# dataBoard.net
KiCad netlist of a schematic drawn in EAGLE
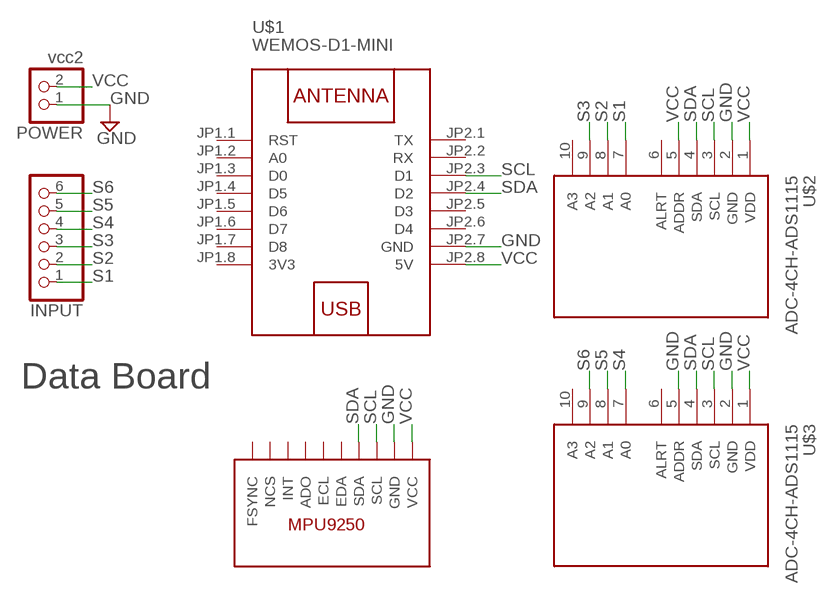
[diagram p0: schematic, sheet 1]

(export (version "E")
  (design (tool "Eeschema 10.0.6"))
  (components
    (comp (ref "INPUT")
      (value "PINHD-1X6")
      (footprint "eagle-import:1X06")
      (libsource (lib "eagle-import") (part "PINHD-1X6"))
    )
    (comp (ref "MPU1")
      (value "MPU9250")
      (footprint "eagle-import:MPU9250")
      (libsource (lib "eagle-import") (part "MPU9250"))
    )
    (comp (ref "POWER")
      (value "vcc2")
      (footprint "eagle-import:1X02")
      (libsource (lib "eagle-import") (part "PINHD-1X2"))
    )
    (comp (ref "U$1")
      (value "WEMOS-D1-MINI")
      (footprint "eagle-import:WEMOS-D1-MINI")
      (libsource (lib "eagle-import") (part "WEMOS-D1-MINI"))
    )
    (comp (ref "U$2")
      (value "ADC-4CH-ADS1115")
      (footprint "eagle-import:ADC-4CH-ADS1115")
      (libsource (lib "eagle-import") (part "ADC-4CH-ADS1115"))
    )
    (comp (ref "U$3")
      (value "ADC-4CH-ADS1115")
      (footprint "eagle-import:ADC-4CH-ADS1115")
      (libsource (lib "eagle-import") (part "ADC-4CH-ADS1115"))
    )
  )
  (nets
    (net (code "1") (name "/3V3") (class "Default")
      (node (ref "U$1") (pin "JP1.8") (pinfunction "3V3_JP1.8") (pintype "power_in"))
    )
    (net (code "2") (name "/S1") (class "Default")
      (node (ref "INPUT") (pin "1") (pinfunction "1_1") (pintype "passive"))
      (node (ref "U$2") (pin "7") (pinfunction "A0_7") (pintype "input"))
    )
    (net (code "3") (name "/S2") (class "Default")
      (node (ref "INPUT") (pin "2") (pinfunction "2_2") (pintype "passive"))
      (node (ref "U$2") (pin "8") (pinfunction "A1_8") (pintype "input"))
    )
    (net (code "4") (name "/S3") (class "Default")
      (node (ref "INPUT") (pin "3") (pinfunction "3_3") (pintype "passive"))
      (node (ref "U$2") (pin "9") (pinfunction "A2_9") (pintype "input"))
    )
    (net (code "5") (name "/S4") (class "Default")
      (node (ref "INPUT") (pin "4") (pinfunction "4_4") (pintype "passive"))
      (node (ref "U$3") (pin "7") (pinfunction "A0_7") (pintype "input"))
    )
    (net (code "6") (name "/S5") (class "Default")
      (node (ref "INPUT") (pin "5") (pinfunction "5_5") (pintype "passive"))
      (node (ref "U$3") (pin "8") (pinfunction "A1_8") (pintype "input"))
    )
    (net (code "7") (name "/S6") (class "Default")
      (node (ref "INPUT") (pin "6") (pinfunction "6_6") (pintype "passive"))
      (node (ref "U$3") (pin "9") (pinfunction "A2_9") (pintype "input"))
    )
    (net (code "8") (name "/SCL") (class "Default")
      (node (ref "MPU1") (pin "SCL") (pinfunction "SCL_SCL") (pintype "bidirectional"))
      (node (ref "U$1") (pin "JP2.3") (pinfunction "D1_JP2.3") (pintype "bidirectional"))
      (node (ref "U$2") (pin "3") (pinfunction "SCL_3") (pintype "bidirectional"))
      (node (ref "U$3") (pin "3") (pinfunction "SCL_3") (pintype "bidirectional"))
    )
    (net (code "9") (name "/SDA") (class "Default")
      (node (ref "MPU1") (pin "SDA") (pinfunction "SDA_SDA") (pintype "bidirectional"))
      (node (ref "U$1") (pin "JP2.4") (pinfunction "D2_JP2.4") (pintype "bidirectional"))
      (node (ref "U$2") (pin "4") (pinfunction "SDA_4") (pintype "bidirectional"))
      (node (ref "U$3") (pin "4") (pinfunction "SDA_4") (pintype "bidirectional"))
    )
    (net (code "10") (name "/VCC") (class "Default")
      (node (ref "MPU1") (pin "VCC") (pinfunction "VCC_VCC") (pintype "bidirectional"))
      (node (ref "POWER") (pin "2") (pinfunction "2_2") (pintype "passive"))
      (node (ref "U$1") (pin "JP2.8") (pinfunction "5V_JP2.8") (pintype "power_in"))
      (node (ref "U$2") (pin "1") (pinfunction "VDD_1") (pintype "power_in"))
      (node (ref "U$2") (pin "5") (pinfunction "ADDR_5") (pintype "bidirectional"))
      (node (ref "U$3") (pin "1") (pinfunction "VDD_1") (pintype "power_in"))
    )
    (net (code "11") (name "GND") (class "Default")
      (node (ref "MPU1") (pin "GND") (pinfunction "GND_GND") (pintype "bidirectional"))
      (node (ref "POWER") (pin "1") (pinfunction "1_1") (pintype "passive"))
      (node (ref "U$1") (pin "JP2.7") (pinfunction "GND_JP2.7") (pintype "power_in"))
      (node (ref "U$2") (pin "2") (pinfunction "GND_2") (pintype "power_in"))
      (node (ref "U$3") (pin "2") (pinfunction "GND_2") (pintype "power_in"))
      (node (ref "U$3") (pin "5") (pinfunction "ADDR_5") (pintype "bidirectional"))
    )
    (net (code "12") (name "unconnected-(MPU1-PadADO)") (class "Default")
      (node (ref "MPU1") (pin "ADO") (pinfunction "ADO_ADO") (pintype "bidirectional"))
    )
    (net (code "13") (name "unconnected-(MPU1-PadECL)") (class "Default")
      (node (ref "MPU1") (pin "ECL") (pinfunction "ECL_ECL") (pintype "bidirectional"))
    )
    (net (code "14") (name "unconnected-(MPU1-PadEDA)") (class "Default")
      (node (ref "MPU1") (pin "EDA") (pinfunction "EDA_EDA") (pintype "bidirectional"))
    )
    (net (code "15") (name "unconnected-(MPU1-PadFSYNC)") (class "Default")
      (node (ref "MPU1") (pin "FSYNC") (pinfunction "FSYNC_FSYNC") (pintype "bidirectional"))
    )
    (net (code "16") (name "unconnected-(MPU1-PadINT)") (class "Default")
      (node (ref "MPU1") (pin "INT") (pinfunction "INT_INT") (pintype "bidirectional"))
    )
    (net (code "17") (name "unconnected-(MPU1-PadNCS)") (class "Default")
      (node (ref "MPU1") (pin "NCS") (pinfunction "NCS_NCS") (pintype "bidirectional"))
    )
    (net (code "18") (name "unconnected-(U$1-A0-PadJP1.2)") (class "Default")
      (node (ref "U$1") (pin "JP1.2") (pinfunction "A0_JP1.2") (pintype "bidirectional"))
    )
    (net (code "19") (name "unconnected-(U$1-D0-PadJP1.3)") (class "Default")
      (node (ref "U$1") (pin "JP1.3") (pinfunction "D0_JP1.3") (pintype "bidirectional"))
    )
    (net (code "20") (name "unconnected-(U$1-D3-PadJP2.5)") (class "Default")
      (node (ref "U$1") (pin "JP2.5") (pinfunction "D3_JP2.5") (pintype "bidirectional"))
    )
    (net (code "21") (name "unconnected-(U$1-D4-PadJP2.6)") (class "Default")
      (node (ref "U$1") (pin "JP2.6") (pinfunction "D4_JP2.6") (pintype "bidirectional"))
    )
    (net (code "22") (name "unconnected-(U$1-D5-PadJP1.4)") (class "Default")
      (node (ref "U$1") (pin "JP1.4") (pinfunction "D5_JP1.4") (pintype "bidirectional"))
    )
    (net (code "23") (name "unconnected-(U$1-D6-PadJP1.5)") (class "Default")
      (node (ref "U$1") (pin "JP1.5") (pinfunction "D6_JP1.5") (pintype "bidirectional"))
    )
    (net (code "24") (name "unconnected-(U$1-D7-PadJP1.6)") (class "Default")
      (node (ref "U$1") (pin "JP1.6") (pinfunction "D7_JP1.6") (pintype "bidirectional"))
    )
    (net (code "25") (name "unconnected-(U$1-D8-PadJP1.7)") (class "Default")
      (node (ref "U$1") (pin "JP1.7") (pinfunction "D8_JP1.7") (pintype "bidirectional"))
    )
    (net (code "26") (name "unconnected-(U$1-RST-PadJP1.1)") (class "Default")
      (node (ref "U$1") (pin "JP1.1") (pinfunction "RST_JP1.1") (pintype "bidirectional"))
    )
    (net (code "27") (name "unconnected-(U$1-RX-PadJP2.2)") (class "Default")
      (node (ref "U$1") (pin "JP2.2") (pinfunction "RX_JP2.2") (pintype "bidirectional"))
    )
    (net (code "28") (name "unconnected-(U$1-TX-PadJP2.1)") (class "Default")
      (node (ref "U$1") (pin "JP2.1") (pinfunction "TX_JP2.1") (pintype "bidirectional"))
    )
    (net (code "29") (name "unconnected-(U$2-A3-Pad10)") (class "Default")
      (node (ref "U$2") (pin "10") (pinfunction "A3_10") (pintype "input"))
    )
    (net (code "30") (name "unconnected-(U$2-ALRT-Pad6)") (class "Default")
      (node (ref "U$2") (pin "6") (pinfunction "ALRT_6") (pintype "bidirectional"))
    )
    (net (code "31") (name "unconnected-(U$3-A3-Pad10)") (class "Default")
      (node (ref "U$3") (pin "10") (pinfunction "A3_10") (pintype "input"))
    )
    (net (code "32") (name "unconnected-(U$3-ALRT-Pad6)") (class "Default")
      (node (ref "U$3") (pin "6") (pinfunction "ALRT_6") (pintype "bidirectional"))
    )
  )
)
